# CAN.net
KiCad netlist of a schematic drawn in Altium Designer
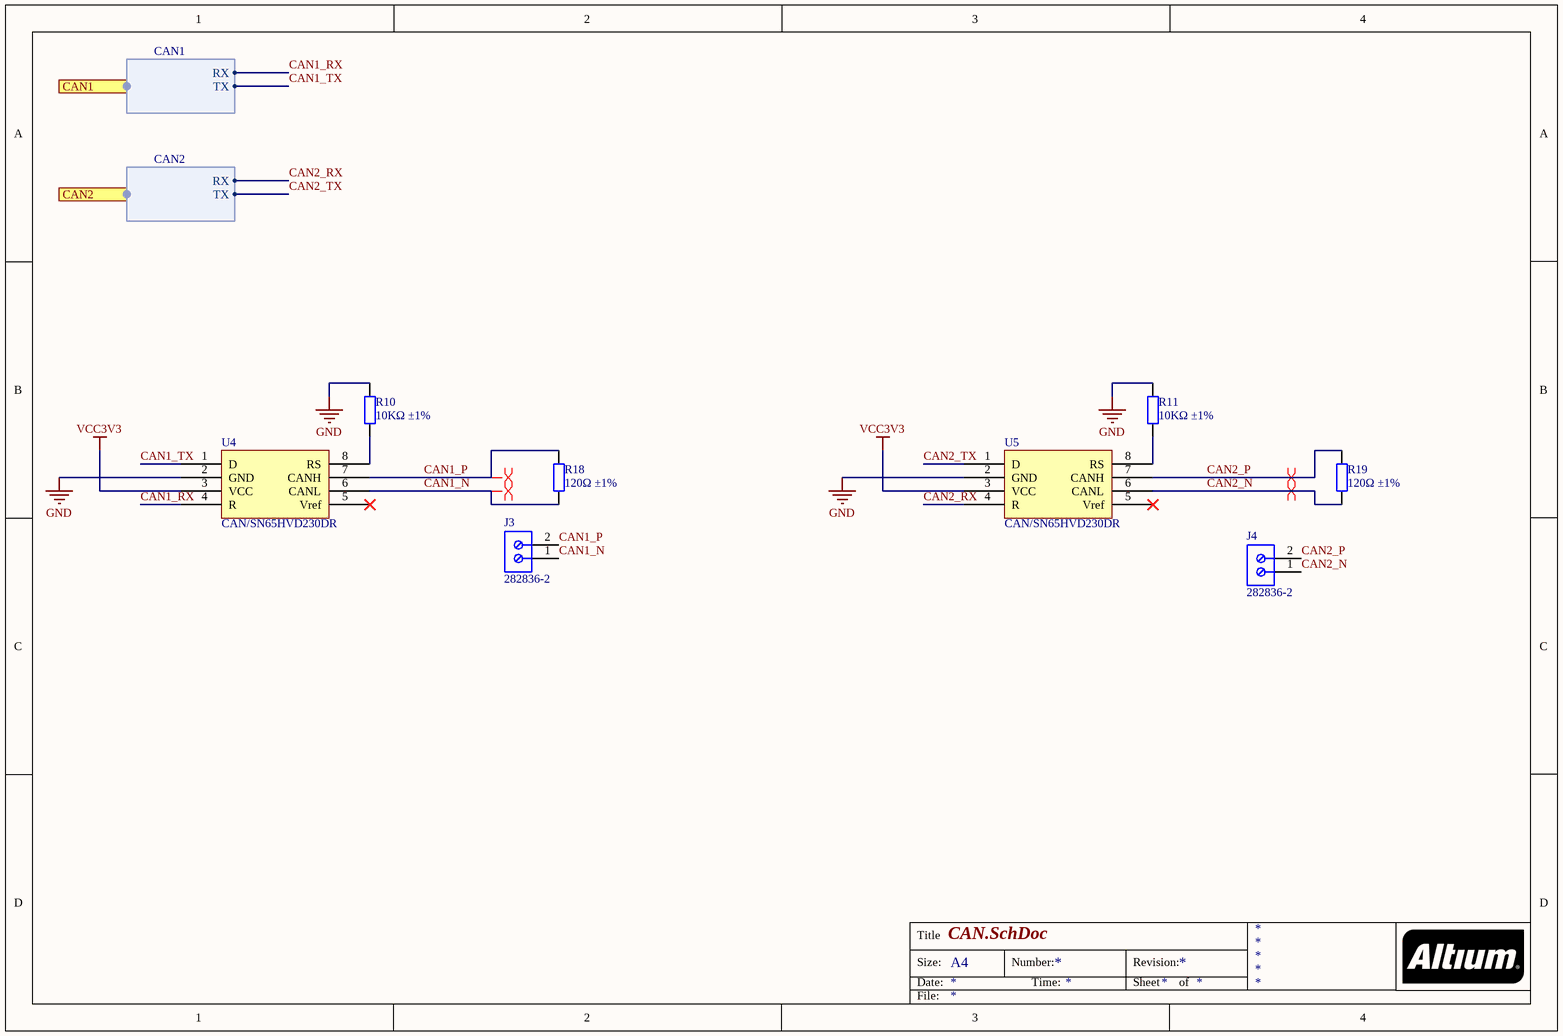
[diagram p0: CAN.SchDoc]

(export (version "E")
  (design (tool "Eeschema 10.0.6"))
  (components
    (comp (ref "J3")
      (value "282836-2")
      (footprint "TECO-282836-2_V")
      (description "Female Header, Pitch 5 mm, 1 x 2 Position, Height 10 mm, Tail Length 3.5 mm, Rohs, Bulk")
      (fields (field (name "VOLTAGE") "300V") (field (name "MANUFACTURER") "TE Connectivity"))
      (libsource (lib "Altium Content Vault") (part "CN-1P-F-TB2"))
    )
    (comp (ref "J4")
      (value "282836-2")
      (footprint "TECO-282836-2_V")
      (description "Female Header, Pitch 5 mm, 1 x 2 Position, Height 10 mm, Tail Length 3.5 mm, Rohs, Bulk")
      (fields (field (name "VOLTAGE") "300V") (field (name "MANUFACTURER") "TE Connectivity"))
      (libsource (lib "Altium Content Vault") (part "CN-1P-F-TB2"))
    )
    (comp (ref "R10")
      (value "10KΩ ±1%")
      (footprint "0402_R")
      (description "Chip resistor")
      (fields (field (name "MANUFACTURER") "Uniroyal Elec") (field (name "PARTNUMBER") "0402WGF1002TCE"))
      (libsource (lib "Miscellaneous Devices LC") (part "0402 10K (1002) 1%"))
    )
    (comp (ref "R11")
      (value "10KΩ ±1%")
      (footprint "0402_R")
      (description "Chip resistor")
      (fields (field (name "MANUFACTURER") "Uniroyal Elec") (field (name "PARTNUMBER") "0402WGF1002TCE"))
      (libsource (lib "Miscellaneous Devices LC") (part "0402 10K (1002) 1%"))
    )
    (comp (ref "R18")
      (value "120Ω ±1%")
      (footprint "0402_R")
      (description "Chip resistor")
      (fields (field (name "MANUFACTURER") "Uniroyal Elec") (field (name "PARTNUMBER") "0402WGF1200TCE"))
      (libsource (lib "Miscellaneous Devices LC") (part "0402 120R (1200) 1%"))
    )
    (comp (ref "R19")
      (value "120Ω ±1%")
      (footprint "0402_R")
      (description "Chip resistor")
      (fields (field (name "MANUFACTURER") "Uniroyal Elec") (field (name "PARTNUMBER") "0402WGF1200TCE"))
      (libsource (lib "Miscellaneous Devices LC") (part "0402 120R (1200) 1%"))
    )
    (comp (ref "U4")
      (value "CAN/SN65HVD230DR")
      (footprint "SOIC-8_150mil")
      (description "CAN")
      (libsource (lib "Miscellaneous Devices LC") (part "CAN/SN65HVD230DR_[C12084]"))
    )
    (comp (ref "U5")
      (value "CAN/SN65HVD230DR")
      (footprint "SOIC-8_150mil")
      (description "CAN")
      (libsource (lib "Miscellaneous Devices LC") (part "CAN/SN65HVD230DR_[C12084]"))
    )
  )
  (nets
    (net (code "3") (name "/CAN1_N") (class "Default")
      (node (ref "J3") (pin "1") (pinfunction "1_1") (pintype "passive"))
      (node (ref "R18") (pin "1") (pinfunction "1_1") (pintype "passive"))
      (node (ref "U4") (pin "6") (pinfunction "CANL_6") (pintype "passive"))
    )
    (net (code "4") (name "/CAN1_P") (class "Default")
      (node (ref "J3") (pin "2") (pinfunction "2_2") (pintype "passive"))
      (node (ref "R18") (pin "2") (pinfunction "2_2") (pintype "passive"))
      (node (ref "U4") (pin "7") (pinfunction "CANH_7") (pintype "passive"))
    )
    (net (code "5") (name "/CAN1_RX") (class "Default")
      (node (ref "U4") (pin "4") (pinfunction "R_4") (pintype "passive"))
    )
    (net (code "6") (name "/CAN1_TX") (class "Default")
      (node (ref "U4") (pin "1") (pinfunction "D_1") (pintype "passive"))
    )
    (net (code "7") (name "/CAN2_N") (class "Default")
      (node (ref "J4") (pin "1") (pinfunction "1_1") (pintype "passive"))
      (node (ref "R19") (pin "1") (pinfunction "1_1") (pintype "passive"))
      (node (ref "U5") (pin "6") (pinfunction "CANL_6") (pintype "passive"))
    )
    (net (code "8") (name "/CAN2_P") (class "Default")
      (node (ref "J4") (pin "2") (pinfunction "2_2") (pintype "passive"))
      (node (ref "R19") (pin "2") (pinfunction "2_2") (pintype "passive"))
      (node (ref "U5") (pin "7") (pinfunction "CANH_7") (pintype "passive"))
    )
    (net (code "9") (name "/CAN2_RX") (class "Default")
      (node (ref "U5") (pin "4") (pinfunction "R_4") (pintype "passive"))
    )
    (net (code "10") (name "/CAN2_TX") (class "Default")
      (node (ref "U5") (pin "1") (pinfunction "D_1") (pintype "passive"))
    )
    (net (code "13") (name "GND") (class "Default")
      (node (ref "R10") (pin "2") (pinfunction "2_2") (pintype "passive"))
      (node (ref "R11") (pin "2") (pinfunction "2_2") (pintype "passive"))
      (node (ref "U4") (pin "2") (pinfunction "GND_2") (pintype "passive"))
      (node (ref "U5") (pin "2") (pinfunction "GND_2") (pintype "passive"))
    )
    (net (code "14") (name "Net-(U4-RS)") (class "Default")
      (node (ref "R10") (pin "1") (pinfunction "1_1") (pintype "passive"))
      (node (ref "U4") (pin "8") (pinfunction "RS_8") (pintype "passive"))
    )
    (net (code "15") (name "Net-(U5-RS)") (class "Default")
      (node (ref "R11") (pin "1") (pinfunction "1_1") (pintype "passive"))
      (node (ref "U5") (pin "8") (pinfunction "RS_8") (pintype "passive"))
    )
    (net (code "16") (name "VCC3V3") (class "Default")
      (node (ref "U4") (pin "3") (pinfunction "VCC_3") (pintype "passive"))
      (node (ref "U5") (pin "3") (pinfunction "VCC_3") (pintype "passive"))
    )
    (net (code "17") (name "unconnected-(U4-Vref-Pad5)") (class "Default")
      (node (ref "U4") (pin "5") (pinfunction "Vref_5") (pintype "passive+no_connect"))
    )
    (net (code "18") (name "unconnected-(U5-Vref-Pad5)") (class "Default")
      (node (ref "U5") (pin "5") (pinfunction "Vref_5") (pintype "passive+no_connect"))
    )
  )
)
